# mainboard_mcu_v1_4.net
KiCad netlist of a schematic drawn in Altium Designer
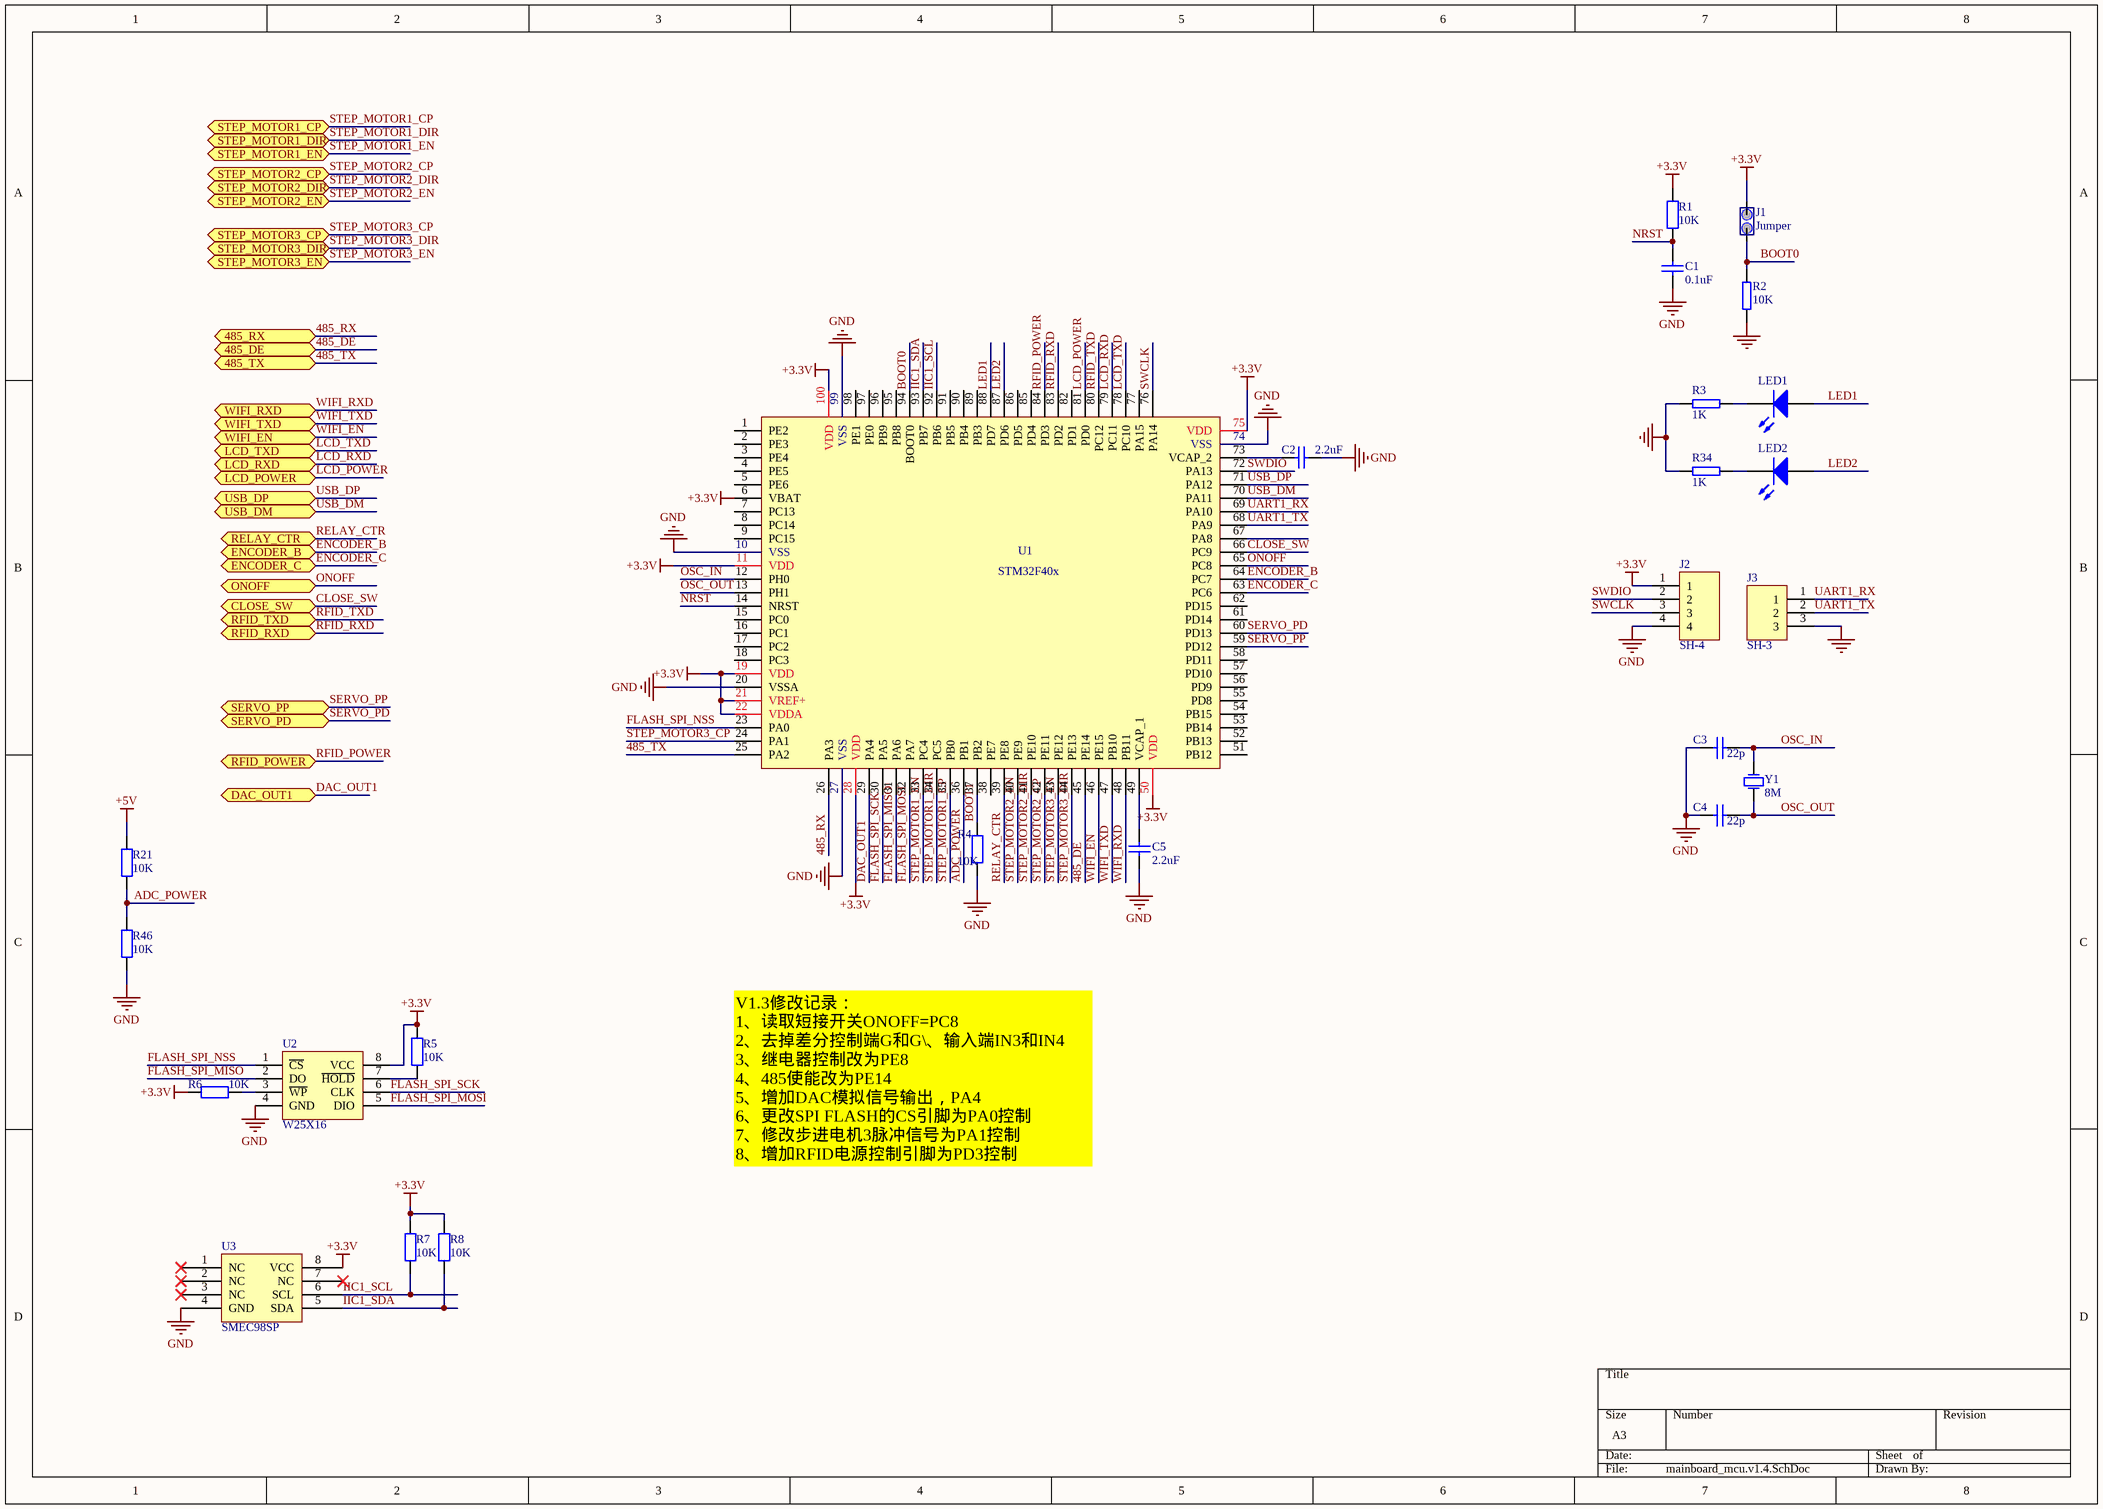
[diagram p0: mainboard_mcu.v1.4.SchDoc]

(export (version "E")
  (design (tool "Eeschema 10.0.6"))
  (components
    (comp (ref "C1")
      (value "0.1uF")
      (footprint "0805")
      (description "Capacitor")
      (fields (field (name "PUBLISHER") "Altium Limited"))
      (libsource (lib "TIAN's Schlib") (part "Cap"))
    )
    (comp (ref "C2")
      (value "2.2uF")
      (footprint "0805")
      (description "Capacitor")
      (fields (field (name "PUBLISHER") "Altium Limited"))
      (libsource (lib "TIAN's Schlib") (part "Cap"))
    )
    (comp (ref "C3")
      (value "22p")
      (footprint "0805")
      (description "Capacitor")
      (fields (field (name "PUBLISHER") "Altium Limited"))
      (libsource (lib "TIAN's Schlib") (part "Cap"))
    )
    (comp (ref "C4")
      (value "22p")
      (footprint "0805")
      (description "Capacitor")
      (fields (field (name "PUBLISHER") "Altium Limited"))
      (libsource (lib "TIAN's Schlib") (part "Cap"))
    )
    (comp (ref "C5")
      (value "2.2uF")
      (footprint "0805")
      (description "Capacitor")
      (fields (field (name "PUBLISHER") "Altium Limited"))
      (libsource (lib "TIAN's Schlib") (part "Cap"))
    )
    (comp (ref "J1") (value "Jumper") (footprint "J254-2") (libsource (lib "Connector") (part "Jumper")))
    (comp (ref "J2") (value "SH-4") (footprint "J254-4") (libsource (lib "Connector") (part "SH-4")))
    (comp (ref "J3") (value "SH-3") (footprint "J2.54-3") (libsource (lib "Connector") (part "SH-3")))
    (comp (ref "LED1")
      (value "GREEN")
      (footprint "LED")
      (description "Typical RED, GREEN, YELLOW, AMBER GaAs LED")
      (fields (field (name "PUBLISHER") "Altium Limited"))
      (libsource (lib "Miscellaneous Devices") (part "LED2"))
    )
    (comp (ref "LED2")
      (value "GREEN")
      (footprint "LED")
      (description "Typical RED, GREEN, YELLOW, AMBER GaAs LED")
      (fields (field (name "PUBLISHER") "Altium Limited"))
      (libsource (lib "Miscellaneous Devices") (part "LED2"))
    )
    (comp (ref "R1")
      (value "10K")
      (footprint "0805")
      (description "Resistor")
      (fields (field (name "PUBLISHER") "Altium Limited"))
      (libsource (lib "TIAN's Schlib") (part "Res2"))
    )
    (comp (ref "R2")
      (value "10K")
      (footprint "0805")
      (description "电阻")
      (libsource (lib "Component") (part "RES"))
    )
    (comp (ref "R3")
      (value "1K")
      (footprint "0805")
      (description "电阻")
      (libsource (lib "Component") (part "RES"))
    )
    (comp (ref "R4")
      (value "10K")
      (footprint "0805")
      (description "Resistor")
      (fields (field (name "PUBLISHER") "Altium Limited"))
      (libsource (lib "") (part "Res2_1"))
    )
    (comp (ref "R5")
      (value "10K")
      (footprint "0805")
      (description "Resistor")
      (fields (field (name "PUBLISHER") "Altium Limited"))
      (libsource (lib "") (part "Res2_1"))
    )
    (comp (ref "R6")
      (value "10K")
      (footprint "0805")
      (description "Resistor")
      (fields (field (name "PUBLISHER") "Altium Limited"))
      (libsource (lib "") (part "Res2_2"))
    )
    (comp (ref "R7")
      (value "10K")
      (footprint "0805")
      (description "Resistor")
      (fields (field (name "PUBLISHER") "Altium Limited"))
      (libsource (lib "TIAN's Schlib") (part "Res2"))
    )
    (comp (ref "R8")
      (value "10K")
      (footprint "0805")
      (description "Resistor")
      (fields (field (name "PUBLISHER") "Altium Limited"))
      (libsource (lib "TIAN's Schlib") (part "Res2"))
    )
    (comp (ref "R21")
      (value "10K")
      (footprint "0805")
      (description "Resistor")
      (fields (field (name "PUBLISHER") "Altium Limited"))
      (libsource (lib "TIAN's Schlib") (part "Res2"))
    )
    (comp (ref "R34")
      (value "1K")
      (footprint "0805")
      (description "电阻")
      (libsource (lib "Component") (part "RES"))
    )
    (comp (ref "R46")
      (value "10K")
      (footprint "0805")
      (description "Resistor")
      (fields (field (name "PUBLISHER") "Altium Limited"))
      (libsource (lib "TIAN's Schlib") (part "Res2"))
    )
    (comp (ref "U1") (value "STM32F40x") (footprint "TQFP100") (libsource (lib "Chip") (part "STM32F40x")))
    (comp (ref "U2") (value "W25X16") (footprint "SOP8") (libsource (lib "Chip") (part "W25X16")))
    (comp (ref "U3") (value "SMEC98SP") (footprint "SO-8") (libsource (lib "Chip") (part "SMEC98SP")))
    (comp (ref "Y1")
      (value "8M")
      (footprint "XTAL")
      (description "Crystal Oscillator")
      (fields (field (name "PUBLISHER") "Altium Limited"))
      (libsource (lib "TIAN's Schlib") (part "X-32.768"))
    )
  )
  (nets
    (net (code "1") (name "+3.3V") (class "Default")
      (node (ref "J1") (pin "2") (pinfunction "2_2") (pintype "passive"))
      (node (ref "J2") (pin "1") (pinfunction "1_1") (pintype "passive"))
      (node (ref "R1") (pin "2") (pinfunction "2_2") (pintype "passive"))
      (node (ref "R5") (pin "1") (pinfunction "1_1") (pintype "passive"))
      (node (ref "R6") (pin "2") (pinfunction "2_2") (pintype "passive"))
      (node (ref "R7") (pin "2") (pinfunction "2_2") (pintype "passive"))
      (node (ref "R8") (pin "2") (pinfunction "2_2") (pintype "passive"))
      (node (ref "U1") (pin "100") (pinfunction "VDD_100") (pintype "passive"))
      (node (ref "U1") (pin "11") (pinfunction "VDD_11") (pintype "passive"))
      (node (ref "U1") (pin "19") (pinfunction "VDD_19") (pintype "passive"))
      (node (ref "U1") (pin "21") (pinfunction "VREF+_21") (pintype "passive"))
      (node (ref "U1") (pin "22") (pinfunction "VDDA_22") (pintype "passive"))
      (node (ref "U1") (pin "28") (pinfunction "VDD_28") (pintype "passive"))
      (node (ref "U1") (pin "50") (pinfunction "VDD_50") (pintype "passive"))
      (node (ref "U1") (pin "6") (pinfunction "VBAT_6") (pintype "passive"))
      (node (ref "U1") (pin "75") (pinfunction "VDD_75") (pintype "passive"))
      (node (ref "U2") (pin "8") (pinfunction "VCC_8") (pintype "passive"))
      (node (ref "U3") (pin "8") (pinfunction "VCC_8") (pintype "passive"))
    )
    (net (code "2") (name "+5V") (class "Default")
      (node (ref "R21") (pin "2") (pinfunction "2_2") (pintype "passive"))
    )
    (net (code "3") (name "/485_DE") (class "Default")
      (node (ref "U1") (pin "45") (pinfunction "PE14_45") (pintype "passive"))
    )
    (net (code "4") (name "/485_RX") (class "Default")
      (node (ref "U1") (pin "26") (pinfunction "PA3_26") (pintype "passive"))
    )
    (net (code "5") (name "/485_TX") (class "Default")
      (node (ref "U1") (pin "25") (pinfunction "PA2_25") (pintype "passive"))
    )
    (net (code "6") (name "/ADC_POWER") (class "Default")
      (node (ref "R21") (pin "1") (pinfunction "1_1") (pintype "passive"))
      (node (ref "R46") (pin "2") (pinfunction "2_2") (pintype "passive"))
      (node (ref "U1") (pin "36") (pinfunction "PB1_36") (pintype "passive"))
    )
    (net (code "7") (name "/BOOT0") (class "Default")
      (node (ref "J1") (pin "1") (pinfunction "1_1") (pintype "passive"))
      (node (ref "R2") (pin "1") (pinfunction "1_1") (pintype "passive"))
      (node (ref "U1") (pin "94") (pinfunction "BOOT0_94") (pintype "passive"))
    )
    (net (code "8") (name "/BOOT1") (class "Default")
      (node (ref "R4") (pin "1") (pinfunction "1_1") (pintype "passive"))
      (node (ref "U1") (pin "37") (pinfunction "PB2_37") (pintype "passive"))
    )
    (net (code "9") (name "/CLOSE_SW") (class "Default")
      (node (ref "U1") (pin "66") (pinfunction "PC9_66") (pintype "passive"))
    )
    (net (code "10") (name "/DAC_OUT1") (class "Default")
      (node (ref "U1") (pin "29") (pinfunction "PA4_29") (pintype "passive"))
    )
    (net (code "11") (name "/ENCODER_B") (class "Default")
      (node (ref "U1") (pin "64") (pinfunction "PC7_64") (pintype "passive"))
    )
    (net (code "12") (name "/ENCODER_C") (class "Default")
      (node (ref "U1") (pin "63") (pinfunction "PC6_63") (pintype "passive"))
    )
    (net (code "13") (name "/FLASH_SPI_MISO") (class "Default")
      (node (ref "U1") (pin "31") (pinfunction "PA6_31") (pintype "passive"))
      (node (ref "U2") (pin "2") (pinfunction "DO_2") (pintype "passive"))
    )
    (net (code "14") (name "/FLASH_SPI_MOSI") (class "Default")
      (node (ref "U1") (pin "32") (pinfunction "PA7_32") (pintype "passive"))
      (node (ref "U2") (pin "5") (pinfunction "DIO_5") (pintype "passive"))
    )
    (net (code "15") (name "/FLASH_SPI_NSS") (class "Default")
      (node (ref "U1") (pin "23") (pinfunction "PA0_23") (pintype "passive"))
      (node (ref "U2") (pin "1") (pinfunction "~{CS}_1") (pintype "passive"))
    )
    (net (code "16") (name "/FLASH_SPI_SCK") (class "Default")
      (node (ref "U1") (pin "30") (pinfunction "PA5_30") (pintype "passive"))
      (node (ref "U2") (pin "6") (pinfunction "CLK_6") (pintype "passive"))
    )
    (net (code "17") (name "/IIC1_SCL") (class "Default")
      (node (ref "R7") (pin "1") (pinfunction "1_1") (pintype "passive"))
      (node (ref "U1") (pin "92") (pinfunction "PB6_92") (pintype "passive"))
      (node (ref "U3") (pin "6") (pinfunction "SCL_6") (pintype "passive"))
    )
    (net (code "18") (name "/IIC1_SDA") (class "Default")
      (node (ref "R8") (pin "1") (pinfunction "1_1") (pintype "passive"))
      (node (ref "U1") (pin "93") (pinfunction "PB7_93") (pintype "passive"))
      (node (ref "U3") (pin "5") (pinfunction "SDA_5") (pintype "passive"))
    )
    (net (code "19") (name "/LCD_POWER") (class "Default")
      (node (ref "U1") (pin "81") (pinfunction "PD0_81") (pintype "passive"))
    )
    (net (code "20") (name "/LCD_RXD") (class "Default")
      (node (ref "U1") (pin "79") (pinfunction "PC11_79") (pintype "passive"))
    )
    (net (code "21") (name "/LCD_TXD") (class "Default")
      (node (ref "U1") (pin "78") (pinfunction "PC10_78") (pintype "passive"))
    )
    (net (code "22") (name "/LED1") (class "Default")
      (node (ref "LED1") (pin "1") (pinfunction "A_1") (pintype "passive"))
      (node (ref "U1") (pin "88") (pinfunction "PD7_88") (pintype "passive"))
    )
    (net (code "23") (name "/LED2") (class "Default")
      (node (ref "LED2") (pin "1") (pinfunction "A_1") (pintype "passive"))
      (node (ref "U1") (pin "87") (pinfunction "PD6_87") (pintype "passive"))
    )
    (net (code "24") (name "/NRST") (class "Default")
      (node (ref "C1") (pin "2") (pinfunction "2_2") (pintype "passive"))
      (node (ref "R1") (pin "1") (pinfunction "1_1") (pintype "passive"))
      (node (ref "U1") (pin "14") (pinfunction "NRST_14") (pintype "passive"))
    )
    (net (code "25") (name "/ONOFF") (class "Default")
      (node (ref "U1") (pin "65") (pinfunction "PC8_65") (pintype "passive"))
    )
    (net (code "26") (name "/OSC_IN") (class "Default")
      (node (ref "C3") (pin "1") (pinfunction "1_1") (pintype "passive"))
      (node (ref "U1") (pin "12") (pinfunction "PH0_12") (pintype "passive"))
      (node (ref "Y1") (pin "2") (pinfunction "OSC2_2") (pintype "passive"))
    )
    (net (code "27") (name "/OSC_OUT") (class "Default")
      (node (ref "C4") (pin "1") (pinfunction "1_1") (pintype "passive"))
      (node (ref "U1") (pin "13") (pinfunction "PH1_13") (pintype "passive"))
      (node (ref "Y1") (pin "1") (pinfunction "OSC1_1") (pintype "passive"))
    )
    (net (code "28") (name "/RELAY_CTR") (class "Default")
      (node (ref "U1") (pin "39") (pinfunction "PE8_39") (pintype "passive"))
    )
    (net (code "29") (name "/RFID_POWER") (class "Default")
      (node (ref "U1") (pin "84") (pinfunction "PD3_84") (pintype "passive"))
    )
    (net (code "30") (name "/RFID_RXD") (class "Default")
      (node (ref "U1") (pin "83") (pinfunction "PD2_83") (pintype "passive"))
    )
    (net (code "31") (name "/RFID_TXD") (class "Default")
      (node (ref "U1") (pin "80") (pinfunction "PC12_80") (pintype "passive"))
    )
    (net (code "32") (name "/SERVO_PD") (class "Default")
      (node (ref "U1") (pin "60") (pinfunction "PD13_60") (pintype "passive"))
    )
    (net (code "33") (name "/SERVO_PP") (class "Default")
      (node (ref "U1") (pin "59") (pinfunction "PD12_59") (pintype "passive"))
    )
    (net (code "34") (name "/STEP_MOTOR1_CP") (class "Default")
      (node (ref "U1") (pin "35") (pinfunction "PB0_35") (pintype "passive"))
    )
    (net (code "35") (name "/STEP_MOTOR1_DIR") (class "Default")
      (node (ref "U1") (pin "34") (pinfunction "PC5_34") (pintype "passive"))
    )
    (net (code "36") (name "/STEP_MOTOR1_EN") (class "Default")
      (node (ref "U1") (pin "33") (pinfunction "PC4_33") (pintype "passive"))
    )
    (net (code "37") (name "/STEP_MOTOR2_CP") (class "Default")
      (node (ref "U1") (pin "42") (pinfunction "PE11_42") (pintype "passive"))
    )
    (net (code "38") (name "/STEP_MOTOR2_DIR") (class "Default")
      (node (ref "U1") (pin "41") (pinfunction "PE10_41") (pintype "passive"))
    )
    (net (code "39") (name "/STEP_MOTOR2_EN") (class "Default")
      (node (ref "U1") (pin "40") (pinfunction "PE9_40") (pintype "passive"))
    )
    (net (code "40") (name "/STEP_MOTOR3_CP") (class "Default")
      (node (ref "U1") (pin "24") (pinfunction "PA1_24") (pintype "passive"))
    )
    (net (code "41") (name "/STEP_MOTOR3_DIR") (class "Default")
      (node (ref "U1") (pin "44") (pinfunction "PE13_44") (pintype "passive"))
    )
    (net (code "42") (name "/STEP_MOTOR3_EN") (class "Default")
      (node (ref "U1") (pin "43") (pinfunction "PE12_43") (pintype "passive"))
    )
    (net (code "43") (name "/SWCLK") (class "Default")
      (node (ref "J2") (pin "3") (pinfunction "3_3") (pintype "passive"))
      (node (ref "U1") (pin "76") (pinfunction "PA14_76") (pintype "passive"))
    )
    (net (code "44") (name "/SWDIO") (class "Default")
      (node (ref "J2") (pin "2") (pinfunction "2_2") (pintype "passive"))
      (node (ref "U1") (pin "72") (pinfunction "PA13_72") (pintype "passive"))
    )
    (net (code "45") (name "/UART1_RX") (class "Default")
      (node (ref "J3") (pin "1") (pinfunction "1_1") (pintype "passive"))
      (node (ref "U1") (pin "69") (pinfunction "PA10_69") (pintype "passive"))
    )
    (net (code "46") (name "/UART1_TX") (class "Default")
      (node (ref "J3") (pin "2") (pinfunction "2_2") (pintype "passive"))
      (node (ref "U1") (pin "68") (pinfunction "PA9_68") (pintype "passive"))
    )
    (net (code "47") (name "/USB_DM") (class "Default")
      (node (ref "U1") (pin "70") (pinfunction "PA11_70") (pintype "passive"))
    )
    (net (code "48") (name "/USB_DP") (class "Default")
      (node (ref "U1") (pin "71") (pinfunction "PA12_71") (pintype "passive"))
    )
    (net (code "49") (name "/WIFI_EN") (class "Default")
      (node (ref "U1") (pin "46") (pinfunction "PE15_46") (pintype "passive"))
    )
    (net (code "50") (name "/WIFI_RXD") (class "Default")
      (node (ref "U1") (pin "48") (pinfunction "PB11_48") (pintype "passive"))
    )
    (net (code "51") (name "/WIFI_TXD") (class "Default")
      (node (ref "U1") (pin "47") (pinfunction "PB10_47") (pintype "passive"))
    )
    (net (code "52") (name "GND") (class "Default")
      (node (ref "C1") (pin "1") (pinfunction "1_1") (pintype "passive"))
      (node (ref "C2") (pin "1") (pinfunction "1_1") (pintype "passive"))
      (node (ref "C3") (pin "2") (pinfunction "2_2") (pintype "passive"))
      (node (ref "C4") (pin "2") (pinfunction "2_2") (pintype "passive"))
      (node (ref "C5") (pin "2") (pinfunction "2_2") (pintype "passive"))
      (node (ref "J2") (pin "4") (pinfunction "4_4") (pintype "passive"))
      (node (ref "J3") (pin "3") (pinfunction "3_3") (pintype "passive"))
      (node (ref "R2") (pin "2") (pinfunction "2_2") (pintype "passive"))
      (node (ref "R3") (pin "2") (pinfunction "2_2") (pintype "passive"))
      (node (ref "R34") (pin "2") (pinfunction "2_2") (pintype "passive"))
      (node (ref "R4") (pin "2") (pinfunction "2_2") (pintype "passive"))
      (node (ref "R46") (pin "1") (pinfunction "1_1") (pintype "passive"))
      (node (ref "U1") (pin "10") (pinfunction "VSS_10") (pintype "passive"))
      (node (ref "U1") (pin "20") (pinfunction "VSSA_20") (pintype "passive"))
      (node (ref "U1") (pin "27") (pinfunction "VSS_27") (pintype "passive"))
      (node (ref "U1") (pin "74") (pinfunction "VSS_74") (pintype "passive"))
      (node (ref "U1") (pin "99") (pinfunction "VSS_99") (pintype "passive"))
      (node (ref "U2") (pin "4") (pinfunction "GND_4") (pintype "passive"))
      (node (ref "U3") (pin "4") (pinfunction "GND_4") (pintype "passive"))
    )
    (net (code "53") (name "Net-(LED1-K)") (class "Default")
      (node (ref "LED1") (pin "2") (pinfunction "K_2") (pintype "passive"))
      (node (ref "R3") (pin "1") (pinfunction "1_1") (pintype "passive"))
    )
    (net (code "54") (name "Net-(LED2-K)") (class "Default")
      (node (ref "LED2") (pin "2") (pinfunction "K_2") (pintype "passive"))
      (node (ref "R34") (pin "1") (pinfunction "1_1") (pintype "passive"))
    )
    (net (code "55") (name "Net-(U1-VCAP_1)") (class "Default")
      (node (ref "C5") (pin "1") (pinfunction "1_1") (pintype "passive"))
      (node (ref "U1") (pin "49") (pinfunction "VCAP_1_49") (pintype "passive"))
    )
    (net (code "56") (name "Net-(U1-VCAP_2)") (class "Default")
      (node (ref "C2") (pin "2") (pinfunction "2_2") (pintype "passive"))
      (node (ref "U1") (pin "73") (pinfunction "VCAP_2_73") (pintype "passive"))
    )
    (net (code "57") (name "Net-(U2-~{HOLD})") (class "Default")
      (node (ref "R5") (pin "2") (pinfunction "2_2") (pintype "passive"))
      (node (ref "U2") (pin "7") (pinfunction "~{HOLD}_7") (pintype "passive"))
    )
    (net (code "58") (name "Net-(U2-~{WP})") (class "Default")
      (node (ref "R6") (pin "1") (pinfunction "1_1") (pintype "passive"))
      (node (ref "U2") (pin "3") (pinfunction "~{WP}_3") (pintype "passive"))
    )
    (net (code "59") (name "unconnected-(U1-PA8-Pad67)") (class "Default")
      (node (ref "U1") (pin "67") (pinfunction "PA8_67") (pintype "passive"))
    )
    (net (code "60") (name "unconnected-(U1-PA15-Pad77)") (class "Default")
      (node (ref "U1") (pin "77") (pinfunction "PA15_77") (pintype "passive"))
    )
    (net (code "61") (name "unconnected-(U1-PB3-Pad89)") (class "Default")
      (node (ref "U1") (pin "89") (pinfunction "PB3_89") (pintype "passive"))
    )
    (net (code "62") (name "unconnected-(U1-PB4-Pad90)") (class "Default")
      (node (ref "U1") (pin "90") (pinfunction "PB4_90") (pintype "passive"))
    )
    (net (code "63") (name "unconnected-(U1-PB5-Pad91)") (class "Default")
      (node (ref "U1") (pin "91") (pinfunction "PB5_91") (pintype "passive"))
    )
    (net (code "64") (name "unconnected-(U1-PB8-Pad95)") (class "Default")
      (node (ref "U1") (pin "95") (pinfunction "PB8_95") (pintype "passive"))
    )
    (net (code "65") (name "unconnected-(U1-PB9-Pad96)") (class "Default")
      (node (ref "U1") (pin "96") (pinfunction "PB9_96") (pintype "passive"))
    )
    (net (code "66") (name "unconnected-(U1-PB12-Pad51)") (class "Default")
      (node (ref "U1") (pin "51") (pinfunction "PB12_51") (pintype "passive"))
    )
    (net (code "67") (name "unconnected-(U1-PB13-Pad52)") (class "Default")
      (node (ref "U1") (pin "52") (pinfunction "PB13_52") (pintype "passive"))
    )
    (net (code "68") (name "unconnected-(U1-PB14-Pad53)") (class "Default")
      (node (ref "U1") (pin "53") (pinfunction "PB14_53") (pintype "passive"))
    )
    (net (code "69") (name "unconnected-(U1-PB15-Pad54)") (class "Default")
      (node (ref "U1") (pin "54") (pinfunction "PB15_54") (pintype "passive"))
    )
    (net (code "70") (name "unconnected-(U1-PC0-Pad15)") (class "Default")
      (node (ref "U1") (pin "15") (pinfunction "PC0_15") (pintype "passive"))
    )
    (net (code "71") (name "unconnected-(U1-PC1-Pad16)") (class "Default")
      (node (ref "U1") (pin "16") (pinfunction "PC1_16") (pintype "passive"))
    )
    (net (code "72") (name "unconnected-(U1-PC2-Pad17)") (class "Default")
      (node (ref "U1") (pin "17") (pinfunction "PC2_17") (pintype "passive"))
    )
    (net (code "73") (name "unconnected-(U1-PC3-Pad18)") (class "Default")
      (node (ref "U1") (pin "18") (pinfunction "PC3_18") (pintype "passive"))
    )
    (net (code "74") (name "unconnected-(U1-PC13-Pad7)") (class "Default")
      (node (ref "U1") (pin "7") (pinfunction "PC13_7") (pintype "passive"))
    )
    (net (code "75") (name "unconnected-(U1-PC14-Pad8)") (class "Default")
      (node (ref "U1") (pin "8") (pinfunction "PC14_8") (pintype "passive"))
    )
    (net (code "76") (name "unconnected-(U1-PC15-Pad9)") (class "Default")
      (node (ref "U1") (pin "9") (pinfunction "PC15_9") (pintype "passive"))
    )
    (net (code "77") (name "unconnected-(U1-PD1-Pad82)") (class "Default")
      (node (ref "U1") (pin "82") (pinfunction "PD1_82") (pintype "passive"))
    )
    (net (code "78") (name "unconnected-(U1-PD4-Pad85)") (class "Default")
      (node (ref "U1") (pin "85") (pinfunction "PD4_85") (pintype "passive"))
    )
    (net (code "79") (name "unconnected-(U1-PD5-Pad86)") (class "Default")
      (node (ref "U1") (pin "86") (pinfunction "PD5_86") (pintype "passive"))
    )
    (net (code "80") (name "unconnected-(U1-PD8-Pad55)") (class "Default")
      (node (ref "U1") (pin "55") (pinfunction "PD8_55") (pintype "passive"))
    )
    (net (code "81") (name "unconnected-(U1-PD9-Pad56)") (class "Default")
      (node (ref "U1") (pin "56") (pinfunction "PD9_56") (pintype "passive"))
    )
    (net (code "82") (name "unconnected-(U1-PD10-Pad57)") (class "Default")
      (node (ref "U1") (pin "57") (pinfunction "PD10_57") (pintype "passive"))
    )
    (net (code "83") (name "unconnected-(U1-PD11-Pad58)") (class "Default")
      (node (ref "U1") (pin "58") (pinfunction "PD11_58") (pintype "passive"))
    )
    (net (code "84") (name "unconnected-(U1-PD14-Pad61)") (class "Default")
      (node (ref "U1") (pin "61") (pinfunction "PD14_61") (pintype "passive"))
    )
    (net (code "85") (name "unconnected-(U1-PD15-Pad62)") (class "Default")
      (node (ref "U1") (pin "62") (pinfunction "PD15_62") (pintype "passive"))
    )
    (net (code "86") (name "unconnected-(U1-PE0-Pad97)") (class "Default")
      (node (ref "U1") (pin "97") (pinfunction "PE0_97") (pintype "passive"))
    )
    (net (code "87") (name "unconnected-(U1-PE1-Pad98)") (class "Default")
      (node (ref "U1") (pin "98") (pinfunction "PE1_98") (pintype "passive"))
    )
    (net (code "88") (name "unconnected-(U1-PE2-Pad1)") (class "Default")
      (node (ref "U1") (pin "1") (pinfunction "PE2_1") (pintype "passive"))
    )
    (net (code "89") (name "unconnected-(U1-PE3-Pad2)") (class "Default")
      (node (ref "U1") (pin "2") (pinfunction "PE3_2") (pintype "passive"))
    )
    (net (code "90") (name "unconnected-(U1-PE4-Pad3)") (class "Default")
      (node (ref "U1") (pin "3") (pinfunction "PE4_3") (pintype "passive"))
    )
    (net (code "91") (name "unconnected-(U1-PE5-Pad4)") (class "Default")
      (node (ref "U1") (pin "4") (pinfunction "PE5_4") (pintype "passive"))
    )
    (net (code "92") (name "unconnected-(U1-PE6-Pad5)") (class "Default")
      (node (ref "U1") (pin "5") (pinfunction "PE6_5") (pintype "passive"))
    )
    (net (code "93") (name "unconnected-(U1-PE7-Pad38)") (class "Default")
      (node (ref "U1") (pin "38") (pinfunction "PE7_38") (pintype "passive"))
    )
    (net (code "94") (name "unconnected-(U3-NC-Pad1)") (class "Default")
      (node (ref "U3") (pin "1") (pinfunction "NC_1") (pintype "passive+no_connect"))
    )
    (net (code "95") (name "unconnected-(U3-NC-Pad2)") (class "Default")
      (node (ref "U3") (pin "2") (pinfunction "NC_2") (pintype "passive+no_connect"))
    )
    (net (code "96") (name "unconnected-(U3-NC-Pad3)") (class "Default")
      (node (ref "U3") (pin "3") (pinfunction "NC_3") (pintype "passive+no_connect"))
    )
    (net (code "97") (name "unconnected-(U3-NC-Pad7)") (class "Default")
      (node (ref "U3") (pin "7") (pinfunction "NC_7") (pintype "passive+no_connect"))
    )
  )
)
